# RP5_Right_Board.net
KiCad netlist of a schematic drawn in Altium Designer
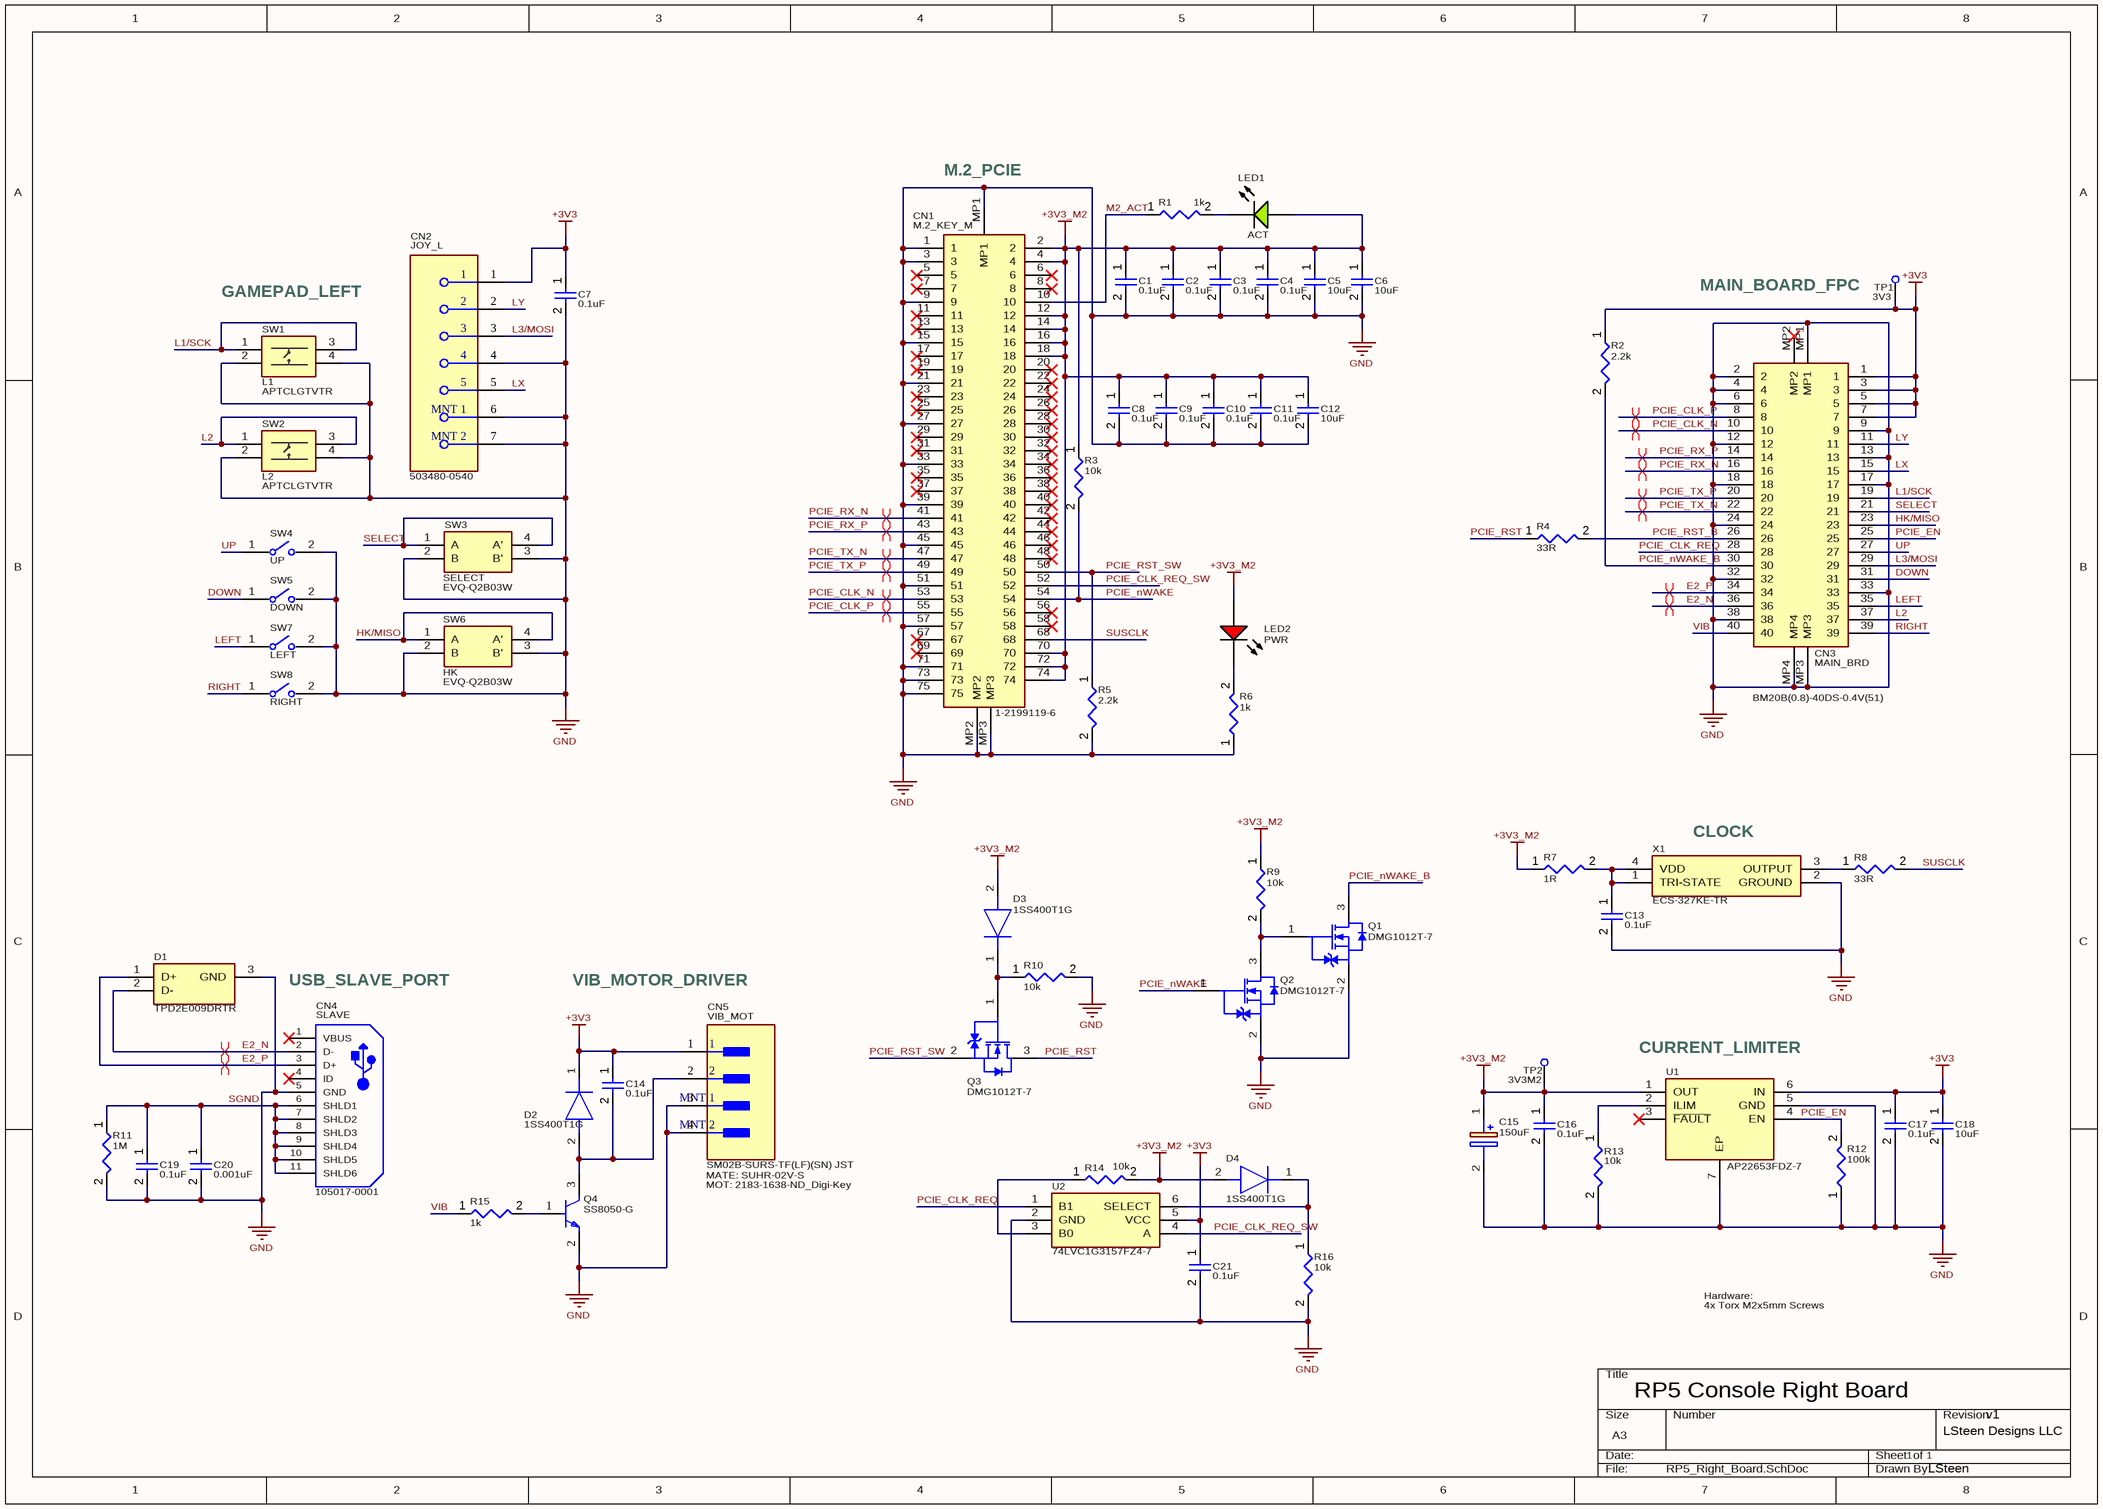
[diagram p0: RP5_Right_Board.SchDoc]

(export (version "E")
  (design (tool "Eeschema 10.0.6"))
  (components
    (comp (ref "C1")
      (value "0.1uF")
      (footprint "CAPC1005X56X25LL10T15")
      (description "Chip Capacitor, 0.1 uF, +/- 5%, 16 V, 0402 (1005 Metric)")
      (fields (field (name "TOLERANCE") "5%"))
      (libsource (lib "Colorado Technical University") (part "CAP-NP-2"))
    )
    (comp (ref "C2")
      (value "0.1uF")
      (footprint "CAPC1005X56X25LL10T15")
      (description "Chip Capacitor, 0.1 uF, +/- 5%, 16 V, 0402 (1005 Metric)")
      (fields (field (name "TOLERANCE") "5%"))
      (libsource (lib "Colorado Technical University") (part "CAP-NP-2"))
    )
    (comp (ref "C3")
      (value "0.1uF")
      (footprint "CAPC1005X56X25LL10T15")
      (description "Chip Capacitor, 0.1 uF, +/- 5%, 16 V, 0402 (1005 Metric)")
      (fields (field (name "TOLERANCE") "5%"))
      (libsource (lib "Colorado Technical University") (part "CAP-NP-2"))
    )
    (comp (ref "C4")
      (value "0.1uF")
      (footprint "CAPC1005X56X25LL10T15")
      (description "Chip Capacitor, 0.1 uF, +/- 5%, 16 V, 0402 (1005 Metric)")
      (fields (field (name "TOLERANCE") "5%"))
      (libsource (lib "Colorado Technical University") (part "CAP-NP-2"))
    )
    (comp (ref "C5")
      (value "10uF")
      (footprint "CAPC0805(2012)145_L")
      (description "Chip Capacitor, 10µF +/-20%, 25V, 0805, Thickness 1.45 mm")
      (fields (field (name "TOLERANCE") "10%"))
      (libsource (lib "Colorado Technical University") (part "CAP-NP-2"))
    )
    (comp (ref "C6")
      (value "10uF")
      (footprint "CAPC0805(2012)145_L")
      (description "Chip Capacitor, 10µF +/-20%, 25V, 0805, Thickness 1.45 mm")
      (fields (field (name "TOLERANCE") "10%"))
      (libsource (lib "Colorado Technical University") (part "CAP-NP-2"))
    )
    (comp (ref "C7")
      (value "0.1uF")
      (footprint "CAPC1005X56X25LL10T15")
      (description "Chip Capacitor, 0.1 uF, +/- 5%, 16 V, 0402 (1005 Metric)")
      (fields (field (name "TOLERANCE") "5%"))
      (libsource (lib "Colorado Technical University") (part "CAP-NP-2"))
    )
    (comp (ref "C8")
      (value "0.1uF")
      (footprint "CAPC1005X56X25LL10T15")
      (description "Chip Capacitor, 0.1 uF, +/- 5%, 16 V, 0402 (1005 Metric)")
      (fields (field (name "TOLERANCE") "5%"))
      (libsource (lib "Colorado Technical University") (part "CAP-NP-2"))
    )
    (comp (ref "C9")
      (value "0.1uF")
      (footprint "CAPC1005X56X25LL10T15")
      (description "Chip Capacitor, 0.1 uF, +/- 5%, 16 V, 0402 (1005 Metric)")
      (fields (field (name "TOLERANCE") "5%"))
      (libsource (lib "Colorado Technical University") (part "CAP-NP-2"))
    )
    (comp (ref "C10")
      (value "0.1uF")
      (footprint "CAPC1005X56X25LL10T15")
      (description "Chip Capacitor, 0.1 uF, +/- 5%, 16 V, 0402 (1005 Metric)")
      (fields (field (name "TOLERANCE") "5%"))
      (libsource (lib "Colorado Technical University") (part "CAP-NP-2"))
    )
    (comp (ref "C11")
      (value "0.1uF")
      (footprint "CAPC1005X56X25LL10T15")
      (description "Chip Capacitor, 0.1 uF, +/- 5%, 16 V, 0402 (1005 Metric)")
      (fields (field (name "TOLERANCE") "5%"))
      (libsource (lib "Colorado Technical University") (part "CAP-NP-2"))
    )
    (comp (ref "C12")
      (value "10uF")
      (footprint "CAPC0805(2012)145_L")
      (description "Chip Capacitor, 10µF +/-20%, 25V, 0805, Thickness 1.45 mm")
      (fields (field (name "TOLERANCE") "10%"))
      (libsource (lib "Colorado Technical University") (part "CAP-NP-2"))
    )
    (comp (ref "C13")
      (value "0.1uF")
      (footprint "CAPC1005X56X25LL10T15")
      (description "Chip Capacitor, 0.1 uF, +/- 5%, 16 V, 0402 (1005 Metric)")
      (fields (field (name "TOLERANCE") "5%"))
      (libsource (lib "Colorado Technical University") (part "CAP-NP-2"))
    )
    (comp (ref "C14")
      (value "0.1uF")
      (footprint "CAPC1005X56X25LL10T15")
      (description "Chip Capacitor, 0.1 uF, +/- 5%, 16 V, 0402 (1005 Metric)")
      (fields (field (name "TOLERANCE") "5%"))
      (libsource (lib "Colorado Technical University") (part "CAP-NP-2"))
    )
    (comp (ref "C15")
      (value "150uF")
      (footprint "SamacSys:CAPPM7344X310N")
      (description "Capacitor Polarised")
      (fields
        (field (name "MANUFACTURER_PART_NUMBER") "TPSD157K016S0125")
        (field (name "MOUSER PART NUMBER") "581-TPSD157K016S0125")
      )
      (libsource (lib "SamacSys") (part "TPSD157K016S0125"))
    )
    (comp (ref "C16")
      (value "0.1uF")
      (footprint "CAPC1005X56X25LL10T15")
      (description "Chip Capacitor, 0.1 uF, +/- 5%, 16 V, 0402 (1005 Metric)")
      (fields (field (name "TOLERANCE") "5%"))
      (libsource (lib "Colorado Technical University") (part "CAP-NP-2"))
    )
    (comp (ref "C17")
      (value "0.1uF")
      (footprint "CAPC1005X56X25LL10T15")
      (description "Chip Capacitor, 0.1 uF, +/- 5%, 16 V, 0402 (1005 Metric)")
      (fields (field (name "TOLERANCE") "5%"))
      (libsource (lib "Colorado Technical University") (part "CAP-NP-2"))
    )
    (comp (ref "C18")
      (value "10uF")
      (footprint "CAPC0805(2012)145_L")
      (description "Chip Capacitor, 10µF +/-20%, 25V, 0805, Thickness 1.45 mm")
      (fields (field (name "TOLERANCE") "10%"))
      (libsource (lib "Colorado Technical University") (part "CAP-NP-2"))
    )
    (comp (ref "C19")
      (value "0.1uF")
      (footprint "CAPC1005X56X25LL10T15")
      (description "Chip Capacitor, 0.1 uF, +/- 5%, 16 V, 0402 (1005 Metric)")
      (fields (field (name "TOLERANCE") "5%"))
      (libsource (lib "Colorado Technical University") (part "CAP-NP-2"))
    )
    (comp (ref "C20")
      (value "0.001uF")
      (footprint "CAPC1005X56X25LL10T15")
      (description "Chip Capacitor, 0.1 uF, +/- 5%, 16 V, 0402 (1005 Metric)")
      (fields (field (name "TOLERANCE") "5%"))
      (libsource (lib "Colorado Technical University") (part "CAP-NP-2"))
    )
    (comp (ref "C21")
      (value "0.1uF")
      (footprint "CAPC1005X56X25LL10T15")
      (description "Chip Capacitor, 0.1 uF, +/- 5%, 16 V, 0402 (1005 Metric)")
      (fields (field (name "TOLERANCE") "5%"))
      (libsource (lib "Colorado Technical University") (part "CAP-NP-2"))
    )
    (comp (ref "CN1")
      (value "M.2_KEY_M")
      (footprint "SamacSys:121991196")
      (description "M.2 PCIE KEY M Connector")
      (fields
        (field (name "MANUFACTURER_PART_NUMBER") "1-2199119-6")
        (field (name "MOUSER PART NUMBER") "571-1-2199119-6")
      )
      (libsource (lib "SamacSys") (part "1-2199119-6"))
    )
    (comp (ref "CN2")
      (value "JOY_L")
      (footprint "FP-503480-0540-MFG")
      (description "503480-0540 Connector FFC/FPC SKT 5 Position 0.5mm Solder Right Angle Surface Mount T/R")
      (libsource (lib "Altium Content Vault") (part "6b037d2877ced340e1c65ac82253790"))
    )
    (comp (ref "CN3")
      (value "MAIN_BRD")
      (footprint "SamacSys:BM20B0840DS04V51")
      (description "Connector")
      (fields
        (field (name "MANUFACTURER_PART_NUMBER") "BM20B(0.8)-40DS-0.4V(51)")
        (field (name "MOUSER PART NUMBER") "798-BM20B0840DS04V51")
      )
      (libsource (lib "SamacSys") (part "BM20B(0.8)-40DS-0.4V(51)"))
    )
    (comp (ref "CN4")
      (value "SLAVE")
      (footprint "105017-0001")
      (description "Micro USB Connector")
      (fields
        (field (name "MANUFACTURER_PART_NUMBER") "105017-0001")
        (field (name "MOUSER PART NUMBER") "538-105017-0001")
      )
      (libsource (lib "SamacSys") (part "105017-0001"))
    )
    (comp (ref "CN5")
      (value "VIB_MOT")
      (footprint "FP-SM02B-SURS-TF_LF_SN-MFG")
      (description "LCSC_CONN HEADER SMD R/A 2POS 0.8MM")
      (libsource (lib "Altium Content Vault") (part "6ebc6fc72a9fd5a6899c7600f385cff"))
    )
    (comp (ref "D1")
      (value "TPD2E009DRTR")
      (footprint "SamacSys:SOTFL35P100X50-3N")
      (description "Integrated Circuit")
      (fields (field (name "MOUSER PART NUMBER") "595-TPD2E009DRTR"))
      (libsource (lib "SamacSys") (part "TPD2E009DRTR"))
    )
    (comp (ref "D2")
      (value "1SS400T1G")
      (footprint "SamacSys:SODFL1608X70N")
      (description "Diode")
      (fields (field (name "MOUSER PART NUMBER") "863-1SS400T1G"))
      (libsource (lib "SamacSys") (part "1SS400T1G"))
    )
    (comp (ref "D3")
      (value "1SS400T1G")
      (footprint "SamacSys:SODFL1608X70N")
      (description "Diode")
      (fields (field (name "MOUSER PART NUMBER") "863-1SS400T1G"))
      (libsource (lib "SamacSys") (part "1SS400T1G"))
    )
    (comp (ref "D4")
      (value "1SS400T1G")
      (footprint "SamacSys:SODFL1608X70N")
      (description "Diode")
      (fields (field (name "MOUSER PART NUMBER") "863-1SS400T1G"))
      (libsource (lib "SamacSys") (part "1SS400T1G"))
    )
    (comp (ref "LED1")
      (value "ACT")
      (footprint "LED_0603")
      (fields (field (name "MPN") "BZ-C0603-K4-E1"))
      (libsource (lib "SamacSys") (part "BZ-C0603-K4-E1"))
    )
    (comp (ref "LED2")
      (value "PWR")
      (footprint "EVRL-0603-2_V")
      (description "Chip LED, Red, 5 V, 25 mA, -40 to 85 degC, 2-Pin SMD (0603), RoHS, Tape and Reel")
      (fields
        (field (name "MANUFACTURER") "Everlight Electronics")
        (field (name "MANUFACTURER PART NUMBER") "19-217/R6C-AL1M2VY/3T")
      )
      (libsource (lib "Altium Content Vault") (part "LED-RED-AK-2"))
    )
    (comp (ref "Q1")
      (value "DMG1012T-7")
      (footprint "DIOD-SOT523-3_V")
      (description "N-Channel Enhancement Mode MOSFET, 20 V, 630 mA, -55 to 150 degC, 3-Pin SOT23, RoHS, Tape and Reel")
      (fields (field (name "MANUFACTURER") "Diodes Inc"))
      (libsource (lib "Altium Content Vault") (part "NEMOS-GSD-3_E"))
    )
    (comp (ref "Q2")
      (value "DMG1012T-7")
      (footprint "DIOD-SOT523-3_V")
      (description "N-Channel Enhancement Mode MOSFET, 20 V, 630 mA, -55 to 150 degC, 3-Pin SOT23, RoHS, Tape and Reel")
      (fields (field (name "MANUFACTURER") "Diodes Inc"))
      (libsource (lib "Altium Content Vault") (part "NEMOS-GSD-3_E"))
    )
    (comp (ref "Q3")
      (value "DMG1012T-7")
      (footprint "DIOD-SOT523-3_V")
      (description "N-Channel Enhancement Mode MOSFET, 20 V, 630 mA, -55 to 150 degC, 3-Pin SOT23, RoHS, Tape and Reel")
      (fields (field (name "MANUFACTURER") "Diodes Inc"))
      (libsource (lib "Altium Content Vault") (part "NEMOS-GSD-3_E"))
    )
    (comp (ref "Q4")
      (value "SS8050-G")
      (footprint "FP-SS8050-G-MFG")
      (description "NPN TRANSISTOR 1.5A 40V SOT-23 R")
      (libsource (lib "Altium Content Vault") (part "2a1388f82443b098dcd57d24ac7632d"))
    )
    (comp (ref "R1")
      (value "1k")
      (footprint "RESC0402(1005)_L")
      (description "Chip Resistor, 1 kOhms, +/-5 %, 63 mW, -55 to 155 degC, 0402")
      (fields (field (name "TOLERANCE") "5%") (field (name "POWER") "63mW"))
      (libsource (lib "Colorado Technical University") (part "RES-2"))
    )
    (comp (ref "R2")
      (value "2.2k")
      (footprint "RESC0402(1005)_L")
      (description "Chip Resistor, 2.2 kOhms, +/-5 %, 63 mW, -55 to 155 degC, 0402")
      (fields (field (name "TOLERANCE") "5%") (field (name "POWER") "63mW"))
      (libsource (lib "Colorado Technical University") (part "RES-2"))
    )
    (comp (ref "R3")
      (value "10k")
      (footprint "RESC0402(1005)_L")
      (description "Chip Resistor, 10 kOhms, +/-5 %, 63 mW, -55 to 155 degC, 0402")
      (fields (field (name "TOLERANCE") "5%") (field (name "POWER") "63mW"))
      (libsource (lib "Colorado Technical University") (part "RES-2"))
    )
    (comp (ref "R4")
      (value "33R")
      (footprint "RESC0402(1005)_L")
      (description "Chip Resistor, 33 Ohms, +/-5 %, 63 mW, -55 to 155 degC, 0402")
      (fields (field (name "TOLERANCE") "5%") (field (name "POWER") "63mW"))
      (libsource (lib "Colorado Technical University") (part "RES-2"))
    )
    (comp (ref "R5")
      (value "2.2k")
      (footprint "RESC0402(1005)_L")
      (description "Chip Resistor, 2.2 kOhms, +/-5 %, 63 mW, -55 to 155 degC, 0402")
      (fields (field (name "TOLERANCE") "5%") (field (name "POWER") "63mW"))
      (libsource (lib "Colorado Technical University") (part "RES-2"))
    )
    (comp (ref "R6")
      (value "1k")
      (footprint "RESC0402(1005)_L")
      (description "Chip Resistor, 1 kOhms, +/-5 %, 63 mW, -55 to 155 degC, 0402")
      (fields (field (name "TOLERANCE") "5%") (field (name "POWER") "63mW"))
      (libsource (lib "Colorado Technical University") (part "RES-2"))
    )
    (comp (ref "R7")
      (value "1R")
      (footprint "RESC0402(1005)_L")
      (description "Chip Resistor, 1 Ohm, +/-5 %, 63 mW, -55 to 155 degC, 0402")
      (fields (field (name "TOLERANCE") "5%") (field (name "POWER") "63mW"))
      (libsource (lib "Colorado Technical University") (part "RES-2"))
    )
    (comp (ref "R8")
      (value "33R")
      (footprint "RESC0402(1005)_L")
      (description "Chip Resistor, 33 Ohms, +/-5 %, 63 mW, -55 to 155 degC, 0402")
      (fields (field (name "TOLERANCE") "5%") (field (name "POWER") "63mW"))
      (libsource (lib "Colorado Technical University") (part "RES-2"))
    )
    (comp (ref "R9")
      (value "10k")
      (footprint "RESC0402(1005)_L")
      (description "Chip Resistor, 10 kOhms, +/-5 %, 63 mW, -55 to 155 degC, 0402")
      (fields (field (name "TOLERANCE") "5%") (field (name "POWER") "63mW"))
      (libsource (lib "Colorado Technical University") (part "RES-2"))
    )
    (comp (ref "R10")
      (value "10k")
      (footprint "RESC0402(1005)_L")
      (description "Chip Resistor, 10 kOhms, +/-5 %, 63 mW, -55 to 155 degC, 0402")
      (fields (field (name "TOLERANCE") "5%") (field (name "POWER") "63mW"))
      (libsource (lib "Colorado Technical University") (part "RES-2"))
    )
    (comp (ref "R11")
      (value "1M")
      (footprint "RESC0402(1005)_L")
      (description "Chip Resistor, 1 MOhms, +/-5 %, 63 mW, -55 to 155 degC, 0402")
      (fields (field (name "TOLERANCE") "5%") (field (name "POWER") "63mW"))
      (libsource (lib "Colorado Technical University") (part "RES-2"))
    )
    (comp (ref "R12")
      (value "100k")
      (footprint "RESC0402(1005)_L")
      (description "Chip Resistor, 100 kOhms, +/-5 %, 63 mW, -55 to 155 degC, 0402")
      (fields (field (name "TOLERANCE") "5%") (field (name "POWER") "63mW"))
      (libsource (lib "Colorado Technical University") (part "RES-2"))
    )
    (comp (ref "R13")
      (value "10k")
      (footprint "RESC0402(1005)_L")
      (description "Chip Resistor, 10 kOhms, +/-5 %, 63 mW, -55 to 155 degC, 0402")
      (fields (field (name "TOLERANCE") "5%") (field (name "POWER") "63mW"))
      (libsource (lib "Colorado Technical University") (part "RES-2"))
    )
    (comp (ref "R14")
      (value "10k")
      (footprint "RESC0402(1005)_L")
      (description "Chip Resistor, 10 kOhms, +/-5 %, 63 mW, -55 to 155 degC, 0402")
      (fields (field (name "TOLERANCE") "5%") (field (name "POWER") "63mW"))
      (libsource (lib "Colorado Technical University") (part "RES-2"))
    )
    (comp (ref "R15")
      (value "1k")
      (footprint "RESC0402(1005)_L")
      (description "Chip Resistor, 1 kOhms, +/-5 %, 63 mW, -55 to 155 degC, 0402")
      (fields (field (name "TOLERANCE") "5%") (field (name "POWER") "63mW"))
      (libsource (lib "Colorado Technical University") (part "RES-2"))
    )
    (comp (ref "R16")
      (value "10k")
      (footprint "RESC0402(1005)_L")
      (description "Chip Resistor, 10 kOhms, +/-5 %, 63 mW, -55 to 155 degC, 0402")
      (fields (field (name "TOLERANCE") "5%") (field (name "POWER") "63mW"))
      (libsource (lib "Colorado Technical University") (part "RES-2"))
    )
    (comp (ref "SW1")
      (value "L1")
      (footprint "SamacSys:APTCLGTVTR")
      (description "Switch")
      (fields
        (field (name "MANUFACTURER_PART_NUMBER") "APTCLGTVTR")
        (field (name "MOUSER PART NUMBER") "642-APTCLGTVTR")
      )
      (libsource (lib "SamacSys") (part "APTCLGTVTR"))
    )
    (comp (ref "SW2")
      (value "L2")
      (footprint "APTCLGTVTR_No_Holes")
      (description "Switch")
      (fields
        (field (name "MANUFACTURER_PART_NUMBER") "APTCLGTVTR")
        (field (name "MOUSER PART NUMBER") "642-APTCLGTVTR")
      )
      (libsource (lib "SamacSys") (part "APTCLGTVTR_NH"))
    )
    (comp (ref "SW3")
      (value "SELECT")
      (footprint "SamacSys:EVQQ2")
      (description "Switch")
      (fields
        (field (name "MANUFACTURER_PART_NUMBER") "EVQ-Q2B03W")
        (field (name "MOUSER PART NUMBER") "667-EVQ-Q2B03W")
      )
      (libsource (lib "SamacSys") (part "EVQ-Q2B03W"))
    )
    (comp (ref "SW4")
      (value "UP")
      (footprint "L4.0-W4.0-CNDV-PAD")
      (description "Conductive Pad Switch")
      (libsource (lib "Schlib1") (part "CNDV_SW"))
    )
    (comp (ref "SW5")
      (value "DOWN")
      (footprint "L4.0-W4.0-CNDV-PAD")
      (description "Conductive Pad Switch")
      (libsource (lib "Schlib1") (part "CNDV_SW"))
    )
    (comp (ref "SW6")
      (value "HK")
      (footprint "SamacSys:EVQQ2")
      (description "Switch")
      (fields
        (field (name "MANUFACTURER_PART_NUMBER") "EVQ-Q2B03W")
        (field (name "MOUSER PART NUMBER") "667-EVQ-Q2B03W")
      )
      (libsource (lib "SamacSys") (part "EVQ-Q2B03W"))
    )
    (comp (ref "SW7")
      (value "LEFT")
      (footprint "L4.0-W4.0-CNDV-PAD")
      (description "Conductive Pad Switch")
      (libsource (lib "Schlib1") (part "CNDV_SW"))
    )
    (comp (ref "SW8")
      (value "RIGHT")
      (footprint "L4.0-W4.0-CNDV-PAD")
      (description "Conductive Pad Switch")
      (libsource (lib "Schlib1") (part "CNDV_SW"))
    )
    (comp (ref "TP1")
      (value "3V3")
      (footprint "TP")
      (description "TestPoint")
      (libsource (lib "Schlib1") (part "TestPoint"))
    )
    (comp (ref "TP2")
      (value "3V3M2")
      (footprint "TP")
      (description "TestPoint")
      (libsource (lib "Schlib1") (part "TestPoint"))
    )
    (comp (ref "U1")
      (value "AP22653FDZ-7")
      (footprint "SamacSys:SON65P200X200X80-7N-D")
      (description "Integrated Circuit")
      (fields (field (name "MOUSER PART NUMBER") "621-AP22653FDZ-7"))
      (libsource (lib "SamacSys") (part "AP22653FDZ-7"))
    )
    (comp (ref "U2")
      (value "74LVC1G3157FZ4-7")
      (footprint "SamacSys:74LVC1G3157FZ47")
      (description "Integrated Circuit")
      (fields (field (name "MOUSER PART NUMBER") "621-74LVC1G3157FZ4-7"))
      (libsource (lib "SamacSys") (part "74LVC1G3157FZ4-7"))
    )
    (comp (ref "X1")
      (value "ECS-327KE-TR")
      (footprint "SamacSys:ECS327KETR")
      (description "Crystal or Oscillator")
      (fields (field (name "MOUSER PART NUMBER") "520-ECS-327KE-TR"))
      (libsource (lib "SamacSys") (part "ECS-327KE-TR"))
    )
  )
  (nets
    (net (code "1") (name "+3V3") (class "Default")
      (node (ref "C14") (pin "1") (pinfunction "1_1") (pintype "passive"))
      (node (ref "C17") (pin "1") (pinfunction "1_1") (pintype "passive"))
      (node (ref "C18") (pin "1") (pinfunction "1_1") (pintype "passive"))
      (node (ref "C21") (pin "1") (pinfunction "1_1") (pintype "passive"))
      (node (ref "C7") (pin "1") (pinfunction "1_1") (pintype "passive"))
      (node (ref "CN2") (pin "1") (pinfunction "1_1") (pintype "passive"))
      (node (ref "CN3") (pin "1") (pinfunction "1_1") (pintype "passive"))
      (node (ref "CN3") (pin "3") (pinfunction "3_3") (pintype "passive"))
      (node (ref "CN3") (pin "5") (pinfunction "5_5") (pintype "passive"))
      (node (ref "CN3") (pin "7") (pinfunction "7_7") (pintype "passive"))
      (node (ref "CN5") (pin "1") (pinfunction "1_1") (pintype "passive"))
      (node (ref "D2") (pin "1") (pinfunction "K_1") (pintype "passive"))
      (node (ref "R2") (pin "1") (pinfunction "1_1") (pintype "passive"))
      (node (ref "TP1") (pin "1") (pinfunction "1_1") (pintype "passive"))
      (node (ref "U1") (pin "6") (pinfunction "IN_6") (pintype "passive"))
      (node (ref "U2") (pin "5") (pinfunction "VCC_5") (pintype "passive"))
    )
    (net (code "2") (name "+3V3_M2") (class "Default")
      (node (ref "C1") (pin "1") (pinfunction "1_1") (pintype "passive"))
      (node (ref "C10") (pin "1") (pinfunction "1_1") (pintype "passive"))
      (node (ref "C11") (pin "1") (pinfunction "1_1") (pintype "passive"))
      (node (ref "C12") (pin "1") (pinfunction "1_1") (pintype "passive"))
      (node (ref "C15") (pin "1") (pinfunction "+_1") (pintype "passive"))
      (node (ref "C16") (pin "1") (pinfunction "1_1") (pintype "passive"))
      (node (ref "C2") (pin "1") (pinfunction "1_1") (pintype "passive"))
      (node (ref "C3") (pin "1") (pinfunction "1_1") (pintype "passive"))
      (node (ref "C4") (pin "1") (pinfunction "1_1") (pintype "passive"))
      (node (ref "C5") (pin "1") (pinfunction "1_1") (pintype "passive"))
      (node (ref "C6") (pin "1") (pinfunction "1_1") (pintype "passive"))
      (node (ref "C8") (pin "1") (pinfunction "1_1") (pintype "passive"))
      (node (ref "C9") (pin "1") (pinfunction "1_1") (pintype "passive"))
      (node (ref "CN1") (pin "12") (pinfunction "12_12") (pintype "passive"))
      (node (ref "CN1") (pin "14") (pinfunction "14_14") (pintype "passive"))
      (node (ref "CN1") (pin "16") (pinfunction "16_16") (pintype "passive"))
      (node (ref "CN1") (pin "18") (pinfunction "18_18") (pintype "passive"))
      (node (ref "CN1") (pin "2") (pinfunction "2_2") (pintype "passive"))
      (node (ref "CN1") (pin "4") (pinfunction "4_4") (pintype "passive"))
      (node (ref "CN1") (pin "70") (pinfunction "70_70") (pintype "passive"))
      (node (ref "CN1") (pin "72") (pinfunction "72_72") (pintype "passive"))
      (node (ref "CN1") (pin "74") (pinfunction "74_74") (pintype "passive"))
      (node (ref "D3") (pin "2") (pinfunction "A_2") (pintype "passive"))
      (node (ref "D4") (pin "2") (pinfunction "A_2") (pintype "passive"))
      (node (ref "LED1") (pin "1") (pinfunction "A_1") (pintype "passive"))
      (node (ref "LED2") (pin "1") (pinfunction "A_1") (pintype "passive"))
      (node (ref "R14") (pin "2") (pinfunction "2_2") (pintype "passive"))
      (node (ref "R3") (pin "1") (pinfunction "1_1") (pintype "passive"))
      (node (ref "R7") (pin "1") (pinfunction "1_1") (pintype "passive"))
      (node (ref "R9") (pin "1") (pinfunction "1_1") (pintype "passive"))
      (node (ref "TP2") (pin "1") (pinfunction "1_1") (pintype "passive"))
      (node (ref "U1") (pin "1") (pinfunction "OUT_1") (pintype "passive"))
    )
    (net (code "3") (name "/DOWN") (class "Default")
      (node (ref "CN3") (pin "31") (pinfunction "31_31") (pintype "passive"))
      (node (ref "SW5") (pin "1") (pinfunction "1_1") (pintype "passive"))
    )
    (net (code "4") (name "/E2_N") (class "Default")
      (node (ref "CN3") (pin "36") (pinfunction "36_36") (pintype "passive"))
      (node (ref "CN4") (pin "2") (pinfunction "D-_2") (pintype "passive"))
      (node (ref "D1") (pin "2") (pinfunction "D-_2") (pintype "passive"))
    )
    (net (code "5") (name "/E2_P") (class "Default")
      (node (ref "CN3") (pin "34") (pinfunction "34_34") (pintype "passive"))
      (node (ref "CN4") (pin "3") (pinfunction "D+_3") (pintype "passive"))
      (node (ref "D1") (pin "1") (pinfunction "D+_1") (pintype "passive"))
    )
    (net (code "6") (name "/HK{slash}MISO") (class "Default")
      (node (ref "CN3") (pin "23") (pinfunction "23_23") (pintype "passive"))
      (node (ref "SW6") (pin "1") (pinfunction "A_1") (pintype "passive"))
      (node (ref "SW6") (pin "4") (pinfunction "A'_4") (pintype "passive"))
    )
    (net (code "7") (name "/L1{slash}SCK") (class "Default")
      (node (ref "CN3") (pin "19") (pinfunction "19_19") (pintype "passive"))
      (node (ref "SW1") (pin "1") (pinfunction "1_1") (pintype "passive"))
      (node (ref "SW1") (pin "3") (pinfunction "3_3") (pintype "passive"))
    )
    (net (code "8") (name "/L2") (class "Default")
      (node (ref "CN3") (pin "37") (pinfunction "37_37") (pintype "passive"))
      (node (ref "SW2") (pin "1") (pinfunction "1_1") (pintype "passive"))
      (node (ref "SW2") (pin "3") (pinfunction "3_3") (pintype "passive"))
    )
    (net (code "9") (name "/L3{slash}MOSI") (class "Default")
      (node (ref "CN2") (pin "3") (pinfunction "3_3") (pintype "passive"))
      (node (ref "CN3") (pin "29") (pinfunction "29_29") (pintype "passive"))
    )
    (net (code "10") (name "/LEFT") (class "Default")
      (node (ref "CN3") (pin "35") (pinfunction "35_35") (pintype "passive"))
      (node (ref "SW7") (pin "1") (pinfunction "1_1") (pintype "passive"))
    )
    (net (code "11") (name "/LX") (class "Default")
      (node (ref "CN2") (pin "5") (pinfunction "5_5") (pintype "passive"))
      (node (ref "CN3") (pin "15") (pinfunction "15_15") (pintype "passive"))
    )
    (net (code "12") (name "/LY") (class "Default")
      (node (ref "CN2") (pin "2") (pinfunction "2_2") (pintype "passive"))
      (node (ref "CN3") (pin "11") (pinfunction "11_11") (pintype "passive"))
    )
    (net (code "13") (name "/M2_ACT") (class "Default")
      (node (ref "CN1") (pin "10") (pinfunction "10_10") (pintype "passive"))
      (node (ref "R1") (pin "1") (pinfunction "1_1") (pintype "passive"))
    )
    (net (code "14") (name "/PCIE_CLK_N") (class "Default")
      (node (ref "CN1") (pin "53") (pinfunction "53_53") (pintype "passive"))
      (node (ref "CN3") (pin "10") (pinfunction "10_10") (pintype "passive"))
    )
    (net (code "15") (name "/PCIE_CLK_P") (class "Default")
      (node (ref "CN1") (pin "55") (pinfunction "55_55") (pintype "passive"))
      (node (ref "CN3") (pin "8") (pinfunction "8_8") (pintype "passive"))
    )
    (net (code "16") (name "/PCIE_CLK_REQ") (class "Default")
      (node (ref "CN3") (pin "28") (pinfunction "28_28") (pintype "passive"))
      (node (ref "U2") (pin "1") (pinfunction "B1_1") (pintype "passive"))
    )
    (net (code "17") (name "/PCIE_CLK_REQ_SW") (class "Default")
      (node (ref "CN1") (pin "52") (pinfunction "52_52") (pintype "passive"))
      (node (ref "U2") (pin "4") (pinfunction "A_4") (pintype "passive"))
    )
    (net (code "18") (name "/PCIE_EN") (class "Default")
      (node (ref "CN3") (pin "25") (pinfunction "25_25") (pintype "passive"))
      (node (ref "R12") (pin "2") (pinfunction "2_2") (pintype "passive"))
      (node (ref "U1") (pin "4") (pinfunction "EN_4") (pintype "passive"))
    )
    (net (code "19") (name "/PCIE_RST") (class "Default")
      (node (ref "Q3") (pin "3") (pinfunction "D_3") (pintype "passive"))
      (node (ref "R4") (pin "1") (pinfunction "1_1") (pintype "passive"))
    )
    (net (code "20") (name "/PCIE_RST_B") (class "Default")
      (node (ref "CN3") (pin "26") (pinfunction "26_26") (pintype "passive"))
      (node (ref "R4") (pin "2") (pinfunction "2_2") (pintype "passive"))
    )
    (net (code "21") (name "/PCIE_RST_SW") (class "Default")
      (node (ref "CN1") (pin "50") (pinfunction "50_50") (pintype "passive"))
      (node (ref "Q3") (pin "2") (pinfunction "S_2") (pintype "passive"))
      (node (ref "R5") (pin "1") (pinfunction "1_1") (pintype "passive"))
    )
    (net (code "22") (name "/PCIE_RX_N") (class "Default")
      (node (ref "CN1") (pin "41") (pinfunction "41_41") (pintype "passive"))
      (node (ref "CN3") (pin "16") (pinfunction "16_16") (pintype "passive"))
    )
    (net (code "23") (name "/PCIE_RX_P") (class "Default")
      (node (ref "CN1") (pin "43") (pinfunction "43_43") (pintype "passive"))
      (node (ref "CN3") (pin "14") (pinfunction "14_14") (pintype "passive"))
    )
    (net (code "24") (name "/PCIE_TX_N") (class "Default")
      (node (ref "CN1") (pin "47") (pinfunction "47_47") (pintype "passive"))
      (node (ref "CN3") (pin "22") (pinfunction "22_22") (pintype "passive"))
    )
    (net (code "25") (name "/PCIE_TX_P") (class "Default")
      (node (ref "CN1") (pin "49") (pinfunction "49_49") (pintype "passive"))
      (node (ref "CN3") (pin "20") (pinfunction "20_20") (pintype "passive"))
    )
    (net (code "26") (name "/PCIE_nWAKE") (class "Default")
      (node (ref "CN1") (pin "54") (pinfunction "54_54") (pintype "passive"))
      (node (ref "Q2") (pin "1") (pinfunction "G_1") (pintype "passive"))
      (node (ref "R3") (pin "2") (pinfunction "2_2") (pintype "passive"))
    )
    (net (code "27") (name "/PCIE_nWAKE_B") (class "Default")
      (node (ref "CN3") (pin "30") (pinfunction "30_30") (pintype "passive"))
      (node (ref "Q1") (pin "3") (pinfunction "D_3") (pintype "passive"))
      (node (ref "R2") (pin "2") (pinfunction "2_2") (pintype "passive"))
    )
    (net (code "28") (name "/RIGHT") (class "Default")
      (node (ref "CN3") (pin "39") (pinfunction "39_39") (pintype "passive"))
      (node (ref "SW8") (pin "1") (pinfunction "1_1") (pintype "passive"))
    )
    (net (code "29") (name "/SELECT") (class "Default")
      (node (ref "CN3") (pin "21") (pinfunction "21_21") (pintype "passive"))
      (node (ref "SW3") (pin "1") (pinfunction "A_1") (pintype "passive"))
      (node (ref "SW3") (pin "4") (pinfunction "A'_4") (pintype "passive"))
    )
    (net (code "30") (name "/SGND") (class "Default")
      (node (ref "C19") (pin "1") (pinfunction "1_1") (pintype "passive"))
      (node (ref "C20") (pin "1") (pinfunction "1_1") (pintype "passive"))
      (node (ref "CN4") (pin "10") (pinfunction "SHLD5_10") (pintype "passive"))
      (node (ref "CN4") (pin "11") (pinfunction "SHLD6_11") (pintype "passive"))
      (node (ref "CN4") (pin "6") (pinfunction "SHLD1_6") (pintype "passive"))
      (node (ref "CN4") (pin "7") (pinfunction "SHLD2_7") (pintype "passive"))
      (node (ref "CN4") (pin "8") (pinfunction "SHLD3_8") (pintype "passive"))
      (node (ref "CN4") (pin "9") (pinfunction "SHLD4_9") (pintype "passive"))
      (node (ref "R11") (pin "1") (pinfunction "1_1") (pintype "passive"))
    )
    (net (code "31") (name "/SUSCLK") (class "Default")
      (node (ref "CN1") (pin "68") (pinfunction "68_68") (pintype "passive"))
      (node (ref "R8") (pin "2") (pinfunction "2_2") (pintype "passive"))
    )
    (net (code "32") (name "/UP") (class "Default")
      (node (ref "CN3") (pin "27") (pinfunction "27_27") (pintype "passive"))
      (node (ref "SW4") (pin "1") (pinfunction "1_1") (pintype "passive"))
    )
    (net (code "33") (name "/VIB") (class "Default")
      (node (ref "CN3") (pin "40") (pinfunction "40_40") (pintype "passive"))
      (node (ref "R15") (pin "1") (pinfunction "1_1") (pintype "passive"))
    )
    (net (code "34") (name "GND") (class "Default")
      (node (ref "C1") (pin "2") (pinfunction "2_2") (pintype "passive"))
      (node (ref "C10") (pin "2") (pinfunction "2_2") (pintype "passive"))
      (node (ref "C11") (pin "2") (pinfunction "2_2") (pintype "passive"))
      (node (ref "C12") (pin "2") (pinfunction "2_2") (pintype "passive"))
      (node (ref "C13") (pin "2") (pinfunction "2_2") (pintype "passive"))
      (node (ref "C15") (pin "2") (pinfunction "-_2") (pintype "passive"))
      (node (ref "C16") (pin "2") (pinfunction "2_2") (pintype "passive"))
      (node (ref "C17") (pin "2") (pinfunction "2_2") (pintype "passive"))
      (node (ref "C18") (pin "2") (pinfunction "2_2") (pintype "passive"))
      (node (ref "C19") (pin "2") (pinfunction "2_2") (pintype "passive"))
      (node (ref "C2") (pin "2") (pinfunction "2_2") (pintype "passive"))
      (node (ref "C20") (pin "2") (pinfunction "2_2") (pintype "passive"))
      (node (ref "C21") (pin "2") (pinfunction "2_2") (pintype "passive"))
      (node (ref "C3") (pin "2") (pinfunction "2_2") (pintype "passive"))
      (node (ref "C4") (pin "2") (pinfunction "2_2") (pintype "passive"))
      (node (ref "C5") (pin "2") (pinfunction "2_2") (pintype "passive"))
      (node (ref "C6") (pin "2") (pinfunction "2_2") (pintype "passive"))
      (node (ref "C7") (pin "2") (pinfunction "2_2") (pintype "passive"))
      (node (ref "C8") (pin "2") (pinfunction "2_2") (pintype "passive"))
      (node (ref "C9") (pin "2") (pinfunction "2_2") (pintype "passive"))
      (node (ref "CN1") (pin "1") (pinfunction "1_1") (pintype "passive"))
      (node (ref "CN1") (pin "15") (pinfunction "15_15") (pintype "passive"))
      (node (ref "CN1") (pin "21") (pinfunction "21_21") (pintype "passive"))
      (node (ref "CN1") (pin "27") (pinfunction "27_27") (pintype "passive"))
      (node (ref "CN1") (pin "3") (pinfunction "3_3") (pintype "passive"))
      (node (ref "CN1") (pin "33") (pinfunction "33_33") (pintype "passive"))
      (node (ref "CN1") (pin "39") (pinfunction "39_39") (pintype "passive"))
      (node (ref "CN1") (pin "45") (pinfunction "45_45") (pintype "passive"))
      (node (ref "CN1") (pin "51") (pinfunction "51_51") (pintype "passive"))
      (node (ref "CN1") (pin "57") (pinfunction "57_57") (pintype "passive"))
      (node (ref "CN1") (pin "71") (pinfunction "71_71") (pintype "passive"))
      (node (ref "CN1") (pin "73") (pinfunction "73_73") (pintype "passive"))
      (node (ref "CN1") (pin "75") (pinfunction "75_75") (pintype "passive"))
      (node (ref "CN1") (pin "9") (pinfunction "9_9") (pintype "passive"))
      (node (ref "CN1") (pin "MP1") (pinfunction "MP1_MP1") (pintype "passive"))
      (node (ref "CN1") (pin "MP2") (pinfunction "MP2_MP2") (pintype "passive"))
      (node (ref "CN1") (pin "MP3") (pinfunction "MP3_MP3") (pintype "passive"))
      (node (ref "CN2") (pin "4") (pinfunction "4_4") (pintype "passive"))
      (node (ref "CN2") (pin "6") (pinfunction "MNT_1_6") (pintype "passive"))
      (node (ref "CN2") (pin "7") (pinfunction "MNT_2_7") (pintype "passive"))
      (node (ref "CN3") (pin "12") (pinfunction "12_12") (pintype "passive"))
      (node (ref "CN3") (pin "13") (pinfunction "13_13") (pintype "passive"))
      (node (ref "CN3") (pin "17") (pinfunction "17_17") (pintype "passive"))
      (node (ref "CN3") (pin "18") (pinfunction "18_18") (pintype "passive"))
      (node (ref "CN3") (pin "2") (pinfunction "2_2") (pintype "passive"))
      (node (ref "CN3") (pin "24") (pinfunction "24_24") (pintype "passive"))
      (node (ref "CN3") (pin "32") (pinfunction "32_32") (pintype "passive"))
      (node (ref "CN3") (pin "33") (pinfunction "33_33") (pintype "passive"))
      (node (ref "CN3") (pin "38") (pinfunction "38_38") (pintype "passive"))
      (node (ref "CN3") (pin "4") (pinfunction "4_4") (pintype "passive"))
      (node (ref "CN3") (pin "6") (pinfunction "6_6") (pintype "passive"))
      (node (ref "CN3") (pin "9") (pinfunction "9_9") (pintype "passive"))
      (node (ref "CN3") (pin "MP1") (pinfunction "MP1_MP1") (pintype "passive"))
      (node (ref "CN3") (pin "MP3") (pinfunction "MP3_MP3") (pintype "passive"))
      (node (ref "CN3") (pin "MP4") (pinfunction "MP4_MP4") (pintype "passive"))
      (node (ref "CN4") (pin "5") (pinfunction "GND_5") (pintype "passive"))
      (node (ref "CN5") (pin "3") (pinfunction "MNT_1_3") (pintype "passive"))
      (node (ref "CN5") (pin "4") (pinfunction "MNT_2_4") (pintype "passive"))
      (node (ref "D1") (pin "3") (pinfunction "GND_3") (pintype "passive"))
      (node (ref "Q1") (pin "2") (pinfunction "S_2") (pintype "passive"))
      (node (ref "Q2") (pin "2") (pinfunction "S_2") (pintype "passive"))
      (node (ref "Q4") (pin "2") (pinfunction "E_2") (pintype "passive"))
      (node (ref "R10") (pin "2") (pinfunction "2_2") (pintype "passive"))
      (node (ref "R11") (pin "2") (pinfunction "2_2") (pintype "passive"))
      (node (ref "R12") (pin "1") (pinfunction "1_1") (pintype "passive"))
      (node (ref "R13") (pin "2") (pinfunction "2_2") (pintype "passive"))
      (node (ref "R16") (pin "2") (pinfunction "2_2") (pintype "passive"))
      (node (ref "R5") (pin "2") (pinfunction "2_2") (pintype "passive"))
      (node (ref "R6") (pin "1") (pinfunction "1_1") (pintype "passive"))
      (node (ref "SW1") (pin "2") (pinfunction "2_2") (pintype "passive"))
      (node (ref "SW1") (pin "4") (pinfunction "4_4") (pintype "passive"))
      (node (ref "SW2") (pin "2") (pinfunction "2_2") (pintype "passive"))
      (node (ref "SW2") (pin "4") (pinfunction "4_4") (pintype "passive"))
      (node (ref "SW3") (pin "2") (pinfunction "B_2") (pintype "passive"))
      (node (ref "SW3") (pin "3") (pinfunction "B'_3") (pintype "passive"))
      (node (ref "SW4") (pin "2") (pinfunction "2_2") (pintype "passive"))
      (node (ref "SW5") (pin "2") (pinfunction "2_2") (pintype "passive"))
      (node (ref "SW6") (pin "2") (pinfunction "B_2") (pintype "passive"))
      (node (ref "SW6") (pin "3") (pinfunction "B'_3") (pintype "passive"))
      (node (ref "SW7") (pin "2") (pinfunction "2_2") (pintype "passive"))
      (node (ref "SW8") (pin "2") (pinfunction "2_2") (pintype "passive"))
      (node (ref "U1") (pin "5") (pinfunction "GND_5") (pintype "passive"))
      (node (ref "U1") (pin "7") (pinfunction "EP_7") (pintype "passive"))
      (node (ref "U2") (pin "2") (pinfunction "GND_2") (pintype "passive"))
      (node (ref "X1") (pin "2") (pinfunction "GROUND_2") (pintype "passive"))
    )
    (net (code "35") (name "Net-(D2-A)") (class "Default")
      (node (ref "C14") (pin "2") (pinfunction "2_2") (pintype "passive"))
      (node (ref "CN5") (pin "2") (pinfunction "2_2") (pintype "passive"))
      (node (ref "D2") (pin "2") (pinfunction "A_2") (pintype "passive"))
      (node (ref "Q4") (pin "3") (pinfunction "C_3") (pintype "passive"))
    )
    (net (code "36") (name "Net-(D3-K)") (class "Default")
      (node (ref "D3") (pin "1") (pinfunction "K_1") (pintype "passive"))
      (node (ref "Q3") (pin "1") (pinfunction "G_1") (pintype "passive"))
      (node (ref "R10") (pin "1") (pinfunction "1_1") (pintype "passive"))
    )
    (net (code "37") (name "Net-(D4-K)") (class "Default")
      (node (ref "D4") (pin "1") (pinfunction "K_1") (pintype "passive"))
      (node (ref "R16") (pin "1") (pinfunction "1_1") (pintype "passive"))
      (node (ref "U2") (pin "6") (pinfunction "SELECT_6") (pintype "passive"))
    )
    (net (code "38") (name "Net-(LED1-K)") (class "Default")
      (node (ref "LED1") (pin "2") (pinfunction "K_2") (pintype "passive"))
      (node (ref "R1") (pin "2") (pinfunction "2_2") (pintype "passive"))
    )
    (net (code "39") (name "Net-(LED2-K)") (class "Default")
      (node (ref "LED2") (pin "2") (pinfunction "K_2") (pintype "passive"))
      (node (ref "R6") (pin "2") (pinfunction "2_2") (pintype "passive"))
    )
    (net (code "40") (name "Net-(Q1-G)") (class "Default")
      (node (ref "Q1") (pin "1") (pinfunction "G_1") (pintype "passive"))
      (node (ref "Q2") (pin "3") (pinfunction "D_3") (pintype "passive"))
      (node (ref "R9") (pin "2") (pinfunction "2_2") (pintype "passive"))
    )
    (net (code "41") (name "Net-(Q4-B)") (class "Default")
      (node (ref "Q4") (pin "1") (pinfunction "B_1") (pintype "passive"))
      (node (ref "R15") (pin "2") (pinfunction "2_2") (pintype "passive"))
    )
    (net (code "42") (name "Net-(U1-ILIM)") (class "Default")
      (node (ref "R13") (pin "1") (pinfunction "1_1") (pintype "passive"))
      (node (ref "U1") (pin "2") (pinfunction "ILIM_2") (pintype "passive"))
    )
    (net (code "43") (name "Net-(U2-B0)") (class "Default")
      (node (ref "R14") (pin "1") (pinfunction "1_1") (pintype "passive"))
      (node (ref "U2") (pin "3") (pinfunction "B0_3") (pintype "passive"))
    )
    (net (code "44") (name "Net-(X1-OUTPUT)") (class "Default")
      (node (ref "R8") (pin "1") (pinfunction "1_1") (pintype "passive"))
      (node (ref "X1") (pin "3") (pinfunction "OUTPUT_3") (pintype "passive"))
    )
    (net (code "45") (name "Net-(X1-TRI-STATE)") (class "Default")
      (node (ref "C13") (pin "1") (pinfunction "1_1") (pintype "passive"))
      (node (ref "R7") (pin "2") (pinfunction "2_2") (pintype "passive"))
      (node (ref "X1") (pin "1") (pinfunction "TRI-STATE_1") (pintype "passive"))
      (node (ref "X1") (pin "4") (pinfunction "VDD_4") (pintype "passive"))
    )
    (net (code "46") (name "unconnected-(CN1-Pad5)") (class "Default")
      (node (ref "CN1") (pin "5") (pinfunction "5_5") (pintype "passive+no_connect"))
    )
    (net (code "47") (name "unconnected-(CN1-Pad6)") (class "Default")
      (node (ref "CN1") (pin "6") (pinfunction "6_6") (pintype "passive+no_connect"))
    )
    (net (code "48") (name "unconnected-(CN1-Pad7)") (class "Default")
      (node (ref "CN1") (pin "7") (pinfunction "7_7") (pintype "passive+no_connect"))
    )
    (net (code "49") (name "unconnected-(CN1-Pad8)") (class "Default")
      (node (ref "CN1") (pin "8") (pinfunction "8_8") (pintype "passive+no_connect"))
    )
    (net (code "50") (name "unconnected-(CN1-Pad11)") (class "Default")
      (node (ref "CN1") (pin "11") (pinfunction "11_11") (pintype "passive+no_connect"))
    )
    (net (code "51") (name "unconnected-(CN1-Pad13)") (class "Default")
      (node (ref "CN1") (pin "13") (pinfunction "13_13") (pintype "passive+no_connect"))
    )
    (net (code "52") (name "unconnected-(CN1-Pad17)") (class "Default")
      (node (ref "CN1") (pin "17") (pinfunction "17_17") (pintype "passive+no_connect"))
    )
    (net (code "53") (name "unconnected-(CN1-Pad19)") (class "Default")
      (node (ref "CN1") (pin "19") (pinfunction "19_19") (pintype "passive+no_connect"))
    )
    (net (code "54") (name "unconnected-(CN1-Pad20)") (class "Default")
      (node (ref "CN1") (pin "20") (pinfunction "20_20") (pintype "passive+no_connect"))
    )
    (net (code "55") (name "unconnected-(CN1-Pad22)") (class "Default")
      (node (ref "CN1") (pin "22") (pinfunction "22_22") (pintype "passive+no_connect"))
    )
    (net (code "56") (name "unconnected-(CN1-Pad23)") (class "Default")
      (node (ref "CN1") (pin "23") (pinfunction "23_23") (pintype "passive+no_connect"))
    )
    (net (code "57") (name "unconnected-(CN1-Pad24)") (class "Default")
      (node (ref "CN1") (pin "24") (pinfunction "24_24") (pintype "passive+no_connect"))
    )
    (net (code "58") (name "unconnected-(CN1-Pad25)") (class "Default")
      (node (ref "CN1") (pin "25") (pinfunction "25_25") (pintype "passive+no_connect"))
    )
    (net (code "59") (name "unconnected-(CN1-Pad26)") (class "Default")
      (node (ref "CN1") (pin "26") (pinfunction "26_26") (pintype "passive+no_connect"))
    )
    (net (code "60") (name "unconnected-(CN1-Pad28)") (class "Default")
      (node (ref "CN1") (pin "28") (pinfunction "28_28") (pintype "passive+no_connect"))
    )
    (net (code "61") (name "unconnected-(CN1-Pad29)") (class "Default")
      (node (ref "CN1") (pin "29") (pinfunction "29_29") (pintype "passive+no_connect"))
    )
    (net (code "62") (name "unconnected-(CN1-Pad30)") (class "Default")
      (node (ref "CN1") (pin "30") (pinfunction "30_30") (pintype "passive+no_connect"))
    )
    (net (code "63") (name "unconnected-(CN1-Pad31)") (class "Default")
      (node (ref "CN1") (pin "31") (pinfunction "31_31") (pintype "passive+no_connect"))
    )
    (net (code "64") (name "unconnected-(CN1-Pad32)") (class "Default")
      (node (ref "CN1") (pin "32") (pinfunction "32_32") (pintype "passive+no_connect"))
    )
    (net (code "65") (name "unconnected-(CN1-Pad34)") (class "Default")
      (node (ref "CN1") (pin "34") (pinfunction "34_34") (pintype "passive+no_connect"))
    )
    (net (code "66") (name "unconnected-(CN1-Pad35)") (class "Default")
      (node (ref "CN1") (pin "35") (pinfunction "35_35") (pintype "passive+no_connect"))
    )
    (net (code "67") (name "unconnected-(CN1-Pad36)") (class "Default")
      (node (ref "CN1") (pin "36") (pinfunction "36_36") (pintype "passive+no_connect"))
    )
    (net (code "68") (name "unconnected-(CN1-Pad37)") (class "Default")
      (node (ref "CN1") (pin "37") (pinfunction "37_37") (pintype "passive+no_connect"))
    )
    (net (code "69") (name "unconnected-(CN1-Pad38)") (class "Default")
      (node (ref "CN1") (pin "38") (pinfunction "38_38") (pintype "passive+no_connect"))
    )
    (net (code "70") (name "unconnected-(CN1-Pad40)") (class "Default")
      (node (ref "CN1") (pin "40") (pinfunction "40_40") (pintype "passive+no_connect"))
    )
    (net (code "71") (name "unconnected-(CN1-Pad42)") (class "Default")
      (node (ref "CN1") (pin "42") (pinfunction "42_42") (pintype "passive+no_connect"))
    )
    (net (code "72") (name "unconnected-(CN1-Pad44)") (class "Default")
      (node (ref "CN1") (pin "44") (pinfunction "44_44") (pintype "passive+no_connect"))
    )
    (net (code "73") (name "unconnected-(CN1-Pad46)") (class "Default")
      (node (ref "CN1") (pin "46") (pinfunction "46_46") (pintype "passive+no_connect"))
    )
    (net (code "74") (name "unconnected-(CN1-Pad48)") (class "Default")
      (node (ref "CN1") (pin "48") (pinfunction "48_48") (pintype "passive+no_connect"))
    )
    (net (code "75") (name "unconnected-(CN1-Pad56)") (class "Default")
      (node (ref "CN1") (pin "56") (pinfunction "56_56") (pintype "passive+no_connect"))
    )
    (net (code "76") (name "unconnected-(CN1-Pad58)") (class "Default")
      (node (ref "CN1") (pin "58") (pinfunction "58_58") (pintype "passive+no_connect"))
    )
    (net (code "77") (name "unconnected-(CN1-Pad67)") (class "Default")
      (node (ref "CN1") (pin "67") (pinfunction "67_67") (pintype "passive+no_connect"))
    )
    (net (code "78") (name "unconnected-(CN1-Pad69)") (class "Default")
      (node (ref "CN1") (pin "69") (pinfunction "69_69") (pintype "passive+no_connect"))
    )
    (net (code "79") (name "unconnected-(CN3-PadMP2)") (class "Default")
      (node (ref "CN3") (pin "MP2") (pinfunction "MP2_MP2") (pintype "passive+no_connect"))
    )
    (net (code "80") (name "unconnected-(CN4-ID-Pad4)") (class "Default")
      (node (ref "CN4") (pin "4") (pinfunction "ID_4") (pintype "passive+no_connect"))
    )
    (net (code "81") (name "unconnected-(CN4-VBUS-Pad1)") (class "Default")
      (node (ref "CN4") (pin "1") (pinfunction "VBUS_1") (pintype "passive+no_connect"))
    )
    (net (code "82") (name "unconnected-(U1-~{FAULT}-Pad3)") (class "Default")
      (node (ref "U1") (pin "3") (pinfunction "~{FAULT}_3") (pintype "passive+no_connect"))
    )
  )
)
